# Light_Control_-_8-16_in_16-32_out_MainBl.net
KiCad netlist of a schematic drawn in Altium Designer
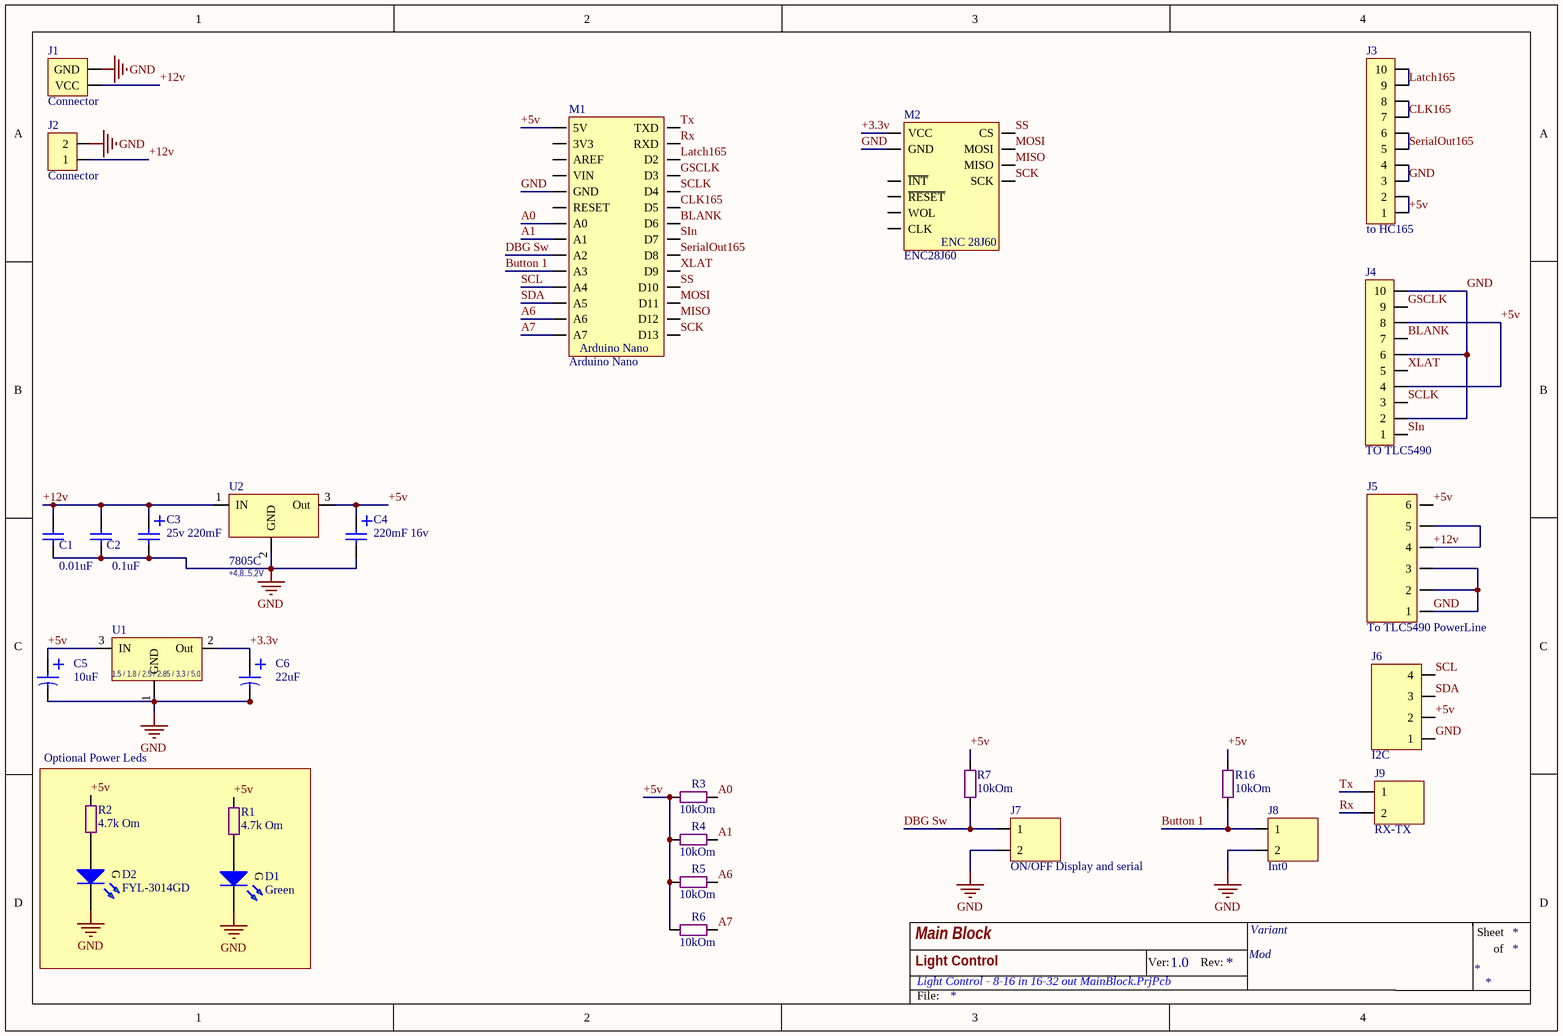
[diagram p0: Light Control - 8-16 in 16-32 out MainBlock.SchDoc]

(export (version "E")
  (design (tool "Eeschema 10.0.6"))
  (components
    (comp (ref "C1")
      (value "0.01uF")
      (footprint "Capacitor:SMD 0805 (2012)")
      (description "Capacitor")
      (libsource (lib "Capacitor") (part "Cap SMD 0402-1812"))
    )
    (comp (ref "C2")
      (value "0.1uF")
      (footprint "Capacitor:SMD 0805 (2012)")
      (description "Capacitor")
      (libsource (lib "Capacitor") (part "Cap SMD 0402-1812"))
    )
    (comp (ref "C3")
      (value "25v 220mF")
      (footprint "Capacitor:Cap E p2mm D6.5xH11")
      (description "Capacitor")
      (libsource (lib "Capacitor") (part "Cap E 220mF x 16V"))
    )
    (comp (ref "C4")
      (value "220mF 16v")
      (footprint "Capacitor:Cap E p2mm D6.5xH11")
      (description "Capacitor")
      (libsource (lib "Capacitor") (part "Cap E 220mF x 16V"))
    )
    (comp (ref "C5")
      (value "10uF")
      (footprint "Capacitor:SMD 1206 Tantal (3216)")
      (description "Capacitor")
      (libsource (lib "Capacitor") (part "Cap Tantal"))
    )
    (comp (ref "C6")
      (value "22uF")
      (footprint "Capacitor:SMD 3528 Tantal (1210)")
      (description "Capacitor")
      (libsource (lib "Capacitor") (part "Cap Tantal"))
    )
    (comp (ref "D1")
      (value "Green")
      (footprint "LED:LED SMD 0805 Green")
      (description "?2v ?20mA")
      (libsource (lib "LED") (part "Led SMD Green"))
    )
    (comp (ref "D2")
      (value "FYL-3014GD")
      (footprint "LED:LED Round 3mm Green")
      (description "2.1v 10mA, 15-30mCd")
      (libsource (lib "LED") (part "Led Round 3mm Green"))
    )
    (comp (ref "J1")
      (value "Connector")
      (footprint "Connector:DC Connector")
      (description "DC Connector")
      (libsource (lib "Connector") (part "DC Connector (PJ-002B)"))
    )
    (comp (ref "J2")
      (value "Connector")
      (footprint "Connector:DG301 5mm 2p")
      (description "DG301 series")
      (libsource (lib "Connector") (part "DG301-5.0-2P12"))
    )
    (comp (ref "J3")
      (value "to HC165")
      (footprint "Connector:LINE 2.54 x 10D (2 x 5) - BH")
      (description "Vert, Dbl line, Male")
      (libsource (lib "Connector") (part "PLD-10 (2 x 5)"))
    )
    (comp (ref "J4")
      (value "TO TLC5490")
      (footprint "Connector:LINE 2.54 x 10D (2 x 5) - BH")
      (description "Vert, Dbl line, Male")
      (libsource (lib "Connector") (part "PLD-10 (2 x 5)"))
    )
    (comp (ref "J5")
      (value "To TLC5490 PowerLine")
      (footprint "Connector:Molex Mini-Fit Jr - 6Pin R")
      (description "Right, Dbl line, Female")
      (libsource (lib "Connector") (part "Molex Mini-Fit Jr - 6 pin"))
    )
    (comp (ref "J6")
      (value "I2C")
      (footprint "Connector:Line 2.54 X 4")
      (description "Vert, Sgl line, Male")
      (libsource (lib "Connector") (part "PLS-4"))
    )
    (comp (ref "J7")
      (value "ON/OFF Display and serial")
      (footprint "Connector:Line 2.54 x 2")
      (description "Vert, Sgl line, Male")
      (libsource (lib "Connector") (part "PLS-2"))
    )
    (comp (ref "J8")
      (value "Int0")
      (footprint "Connector:Line 2.54 x 2")
      (description "Vert, Sgl line, Male")
      (libsource (lib "Connector") (part "PLS-2"))
    )
    (comp (ref "J9")
      (value "RX-TX")
      (footprint "Connector:Line 2.54 x 2")
      (description "Vert, Sgl line, Male")
      (libsource (lib "Connector") (part "PLS-2"))
    )
    (comp (ref "M1")
      (value "Arduino Nano")
      (footprint "Modules:Arduino Nano")
      (libsource (lib "Modules") (part "Arduino Nano"))
    )
    (comp (ref "M2")
      (value "ENC28J60")
      (footprint "Modules:ENC28J60 MiNi")
      (libsource (lib "Modules") (part "ENC28J60"))
    )
    (comp (ref "R1")
      (value "4.7k Om")
      (footprint "PassiveComponents:SMD 0805 (2012)")
      (libsource (lib "PassiveComponents") (part "Res All Types"))
    )
    (comp (ref "R2")
      (value "4.7k Om")
      (footprint "PassiveComponents:SMD 0805 (2012)")
      (libsource (lib "PassiveComponents") (part "Res All Types"))
    )
    (comp (ref "R3")
      (value "10kOm")
      (footprint "PassiveComponents:SMD 0805 (2012)")
      (libsource (lib "PassiveComponents") (part "Res All Types"))
    )
    (comp (ref "R4")
      (value "10kOm")
      (footprint "PassiveComponents:SMD 0805 (2012)")
      (libsource (lib "PassiveComponents") (part "Res All Types"))
    )
    (comp (ref "R5")
      (value "10kOm")
      (footprint "PassiveComponents:SMD 0805 (2012)")
      (libsource (lib "PassiveComponents") (part "Res All Types"))
    )
    (comp (ref "R6")
      (value "10kOm")
      (footprint "PassiveComponents:SMD 0805 (2012)")
      (libsource (lib "PassiveComponents") (part "Res All Types"))
    )
    (comp (ref "R7")
      (value "10kOm")
      (footprint "PassiveComponents:SMD 0805 (2012)")
      (libsource (lib "PassiveComponents") (part "Res All Types"))
    )
    (comp (ref "R16")
      (value "10kOm")
      (footprint "PassiveComponents:SMD 0805 (2012)")
      (libsource (lib "PassiveComponents") (part "Res All Types"))
    )
    (comp (ref "U1")
      (value "AMS1117 1.5 / 1.8 / 2.5 / 2.85 / 3.3 / 5.0")
      (footprint "GeneralCases:SOT-223-3 (AMS)")
      (description "Voltage Regulator SOT-223-3")
      (fields (field (name "V OUT") "1.5 / 1.8 / 2.5 / 2.85 / 3.3 / 5.0"))
      (libsource (lib "PowerAdjusment") (part "AMS1117_FIX"))
    )
    (comp (ref "U2")
      (value "7805C")
      (footprint "GeneralCases:D-PAK")
      (description "Voltage Regulator")
      (fields (field (name "MANUFACTURER") "Интеграл") (field (name "V OUT") "+4,8..5,2V"))
      (libsource (lib "PowerAdjusment") (part "7805C"))
    )
  )
  (nets
    (net (code "1") (name "/+3.3v") (class "Default")
      (node (ref "C6") (pin "VCC") (pinfunction "1_VCC") (pintype "passive"))
      (node (ref "M2") (pin "VCC") (pinfunction "VCC_VCC") (pintype "passive"))
      (node (ref "U1") (pin "2") (pinfunction "Out_2") (pintype "power_in"))
    )
    (net (code "2") (name "/+5v") (class "Default")
      (node (ref "C4") (pin "1") (pinfunction "1_1") (pintype "passive"))
      (node (ref "C5") (pin "VCC") (pinfunction "1_VCC") (pintype "passive"))
      (node (ref "J3") (pin "1") (pinfunction "1_1") (pintype "passive"))
      (node (ref "J3") (pin "2") (pinfunction "2_2") (pintype "passive"))
      (node (ref "J4") (pin "4") (pinfunction "4_4") (pintype "passive"))
      (node (ref "J4") (pin "8") (pinfunction "8_8") (pintype "passive"))
      (node (ref "J5") (pin "6") (pinfunction "6_6") (pintype "passive"))
      (node (ref "J6") (pin "2") (pinfunction "2_2") (pintype "passive"))
      (node (ref "M1") (pin "5V") (pinfunction "5V_5V") (pintype "passive"))
      (node (ref "R1") (pin "1") (pinfunction "1_1") (pintype "passive"))
      (node (ref "R16") (pin "2") (pinfunction "2_2") (pintype "passive"))
      (node (ref "R2") (pin "1") (pinfunction "1_1") (pintype "passive"))
      (node (ref "R3") (pin "2") (pinfunction "2_2") (pintype "passive"))
      (node (ref "R4") (pin "2") (pinfunction "2_2") (pintype "passive"))
      (node (ref "R5") (pin "2") (pinfunction "2_2") (pintype "passive"))
      (node (ref "R6") (pin "2") (pinfunction "2_2") (pintype "passive"))
      (node (ref "R7") (pin "2") (pinfunction "2_2") (pintype "passive"))
      (node (ref "U1") (pin "3") (pinfunction "IN_3") (pintype "power_in"))
      (node (ref "U2") (pin "3") (pinfunction "Out_3") (pintype "power_in"))
    )
    (net (code "3") (name "/+12v") (class "Default")
      (node (ref "C1") (pin "1") (pinfunction "1_1") (pintype "passive"))
      (node (ref "C2") (pin "1") (pinfunction "1_1") (pintype "passive"))
      (node (ref "C3") (pin "1") (pinfunction "1_1") (pintype "passive"))
      (node (ref "J1") (pin "VCC") (pinfunction "VCC_VCC") (pintype "passive"))
      (node (ref "J2") (pin "1") (pinfunction "1_1") (pintype "passive"))
      (node (ref "J5") (pin "4") (pinfunction "4_4") (pintype "passive"))
      (node (ref "J5") (pin "5") (pinfunction "5_5") (pintype "passive"))
      (node (ref "U2") (pin "1") (pinfunction "IN_1") (pintype "power_in"))
    )
    (net (code "4") (name "/A0") (class "Default")
      (node (ref "M1") (pin "A0") (pinfunction "A0_A0") (pintype "passive"))
      (node (ref "R3") (pin "1") (pinfunction "1_1") (pintype "passive"))
    )
    (net (code "5") (name "/A1") (class "Default")
      (node (ref "M1") (pin "A1") (pinfunction "A1_A1") (pintype "passive"))
      (node (ref "R4") (pin "1") (pinfunction "1_1") (pintype "passive"))
    )
    (net (code "6") (name "/A6") (class "Default")
      (node (ref "M1") (pin "A6") (pinfunction "A6_A6") (pintype "passive"))
      (node (ref "R5") (pin "1") (pinfunction "1_1") (pintype "passive"))
    )
    (net (code "7") (name "/A7") (class "Default")
      (node (ref "M1") (pin "A7") (pinfunction "A7_A7") (pintype "passive"))
      (node (ref "R6") (pin "1") (pinfunction "1_1") (pintype "passive"))
    )
    (net (code "8") (name "/BLANK") (class "Default")
      (node (ref "J4") (pin "7") (pinfunction "7_7") (pintype "passive"))
      (node (ref "M1") (pin "D6") (pinfunction "D6_D6") (pintype "passive"))
    )
    (net (code "9") (name "/Button 1") (class "Default")
      (node (ref "J8") (pin "1") (pinfunction "1_1") (pintype "passive"))
      (node (ref "M1") (pin "A3") (pinfunction "A3_A3") (pintype "passive"))
      (node (ref "R16") (pin "1") (pinfunction "1_1") (pintype "passive"))
    )
    (net (code "10") (name "/CLK165") (class "Default")
      (node (ref "J3") (pin "7") (pinfunction "7_7") (pintype "passive"))
      (node (ref "J3") (pin "8") (pinfunction "8_8") (pintype "passive"))
      (node (ref "M1") (pin "D5") (pinfunction "D5_D5") (pintype "passive"))
    )
    (net (code "11") (name "/DBG Sw") (class "Default")
      (node (ref "J7") (pin "1") (pinfunction "1_1") (pintype "passive"))
      (node (ref "M1") (pin "A2") (pinfunction "A2_A2") (pintype "passive"))
      (node (ref "R7") (pin "1") (pinfunction "1_1") (pintype "passive"))
    )
    (net (code "12") (name "/GSCLK") (class "Default")
      (node (ref "J4") (pin "9") (pinfunction "9_9") (pintype "passive"))
      (node (ref "M1") (pin "D3") (pinfunction "D3_D3") (pintype "passive"))
    )
    (net (code "13") (name "/Latch165") (class "Default")
      (node (ref "J3") (pin "10") (pinfunction "10_10") (pintype "passive"))
      (node (ref "J3") (pin "9") (pinfunction "9_9") (pintype "passive"))
      (node (ref "M1") (pin "D2") (pinfunction "D2_D2") (pintype "passive"))
    )
    (net (code "14") (name "/MISO") (class "Default")
      (node (ref "M1") (pin "D12") (pinfunction "D12_D12") (pintype "passive"))
      (node (ref "M2") (pin "MISO") (pinfunction "MISO_MISO") (pintype "passive"))
    )
    (net (code "15") (name "/MOSI") (class "Default")
      (node (ref "M1") (pin "D11") (pinfunction "D11_D11") (pintype "passive"))
      (node (ref "M2") (pin "MOSI") (pinfunction "MOSI_MOSI") (pintype "passive"))
    )
    (net (code "16") (name "/Rx") (class "Default")
      (node (ref "J9") (pin "2") (pinfunction "2_2") (pintype "passive"))
      (node (ref "M1") (pin "RXD") (pinfunction "RXD_RXD") (pintype "passive"))
    )
    (net (code "17") (name "/SCK") (class "Default")
      (node (ref "M1") (pin "D13") (pinfunction "D13_D13") (pintype "passive"))
      (node (ref "M2") (pin "SCK") (pinfunction "SCK_SCK") (pintype "passive"))
    )
    (net (code "18") (name "/SCL") (class "Default")
      (node (ref "J6") (pin "4") (pinfunction "4_4") (pintype "passive"))
      (node (ref "M1") (pin "A4") (pinfunction "A4_A4") (pintype "passive"))
    )
    (net (code "19") (name "/SCLK") (class "Default")
      (node (ref "J4") (pin "3") (pinfunction "3_3") (pintype "passive"))
      (node (ref "M1") (pin "D4") (pinfunction "D4_D4") (pintype "passive"))
    )
    (net (code "20") (name "/SDA") (class "Default")
      (node (ref "J6") (pin "3") (pinfunction "3_3") (pintype "passive"))
      (node (ref "M1") (pin "A5") (pinfunction "A5_A5") (pintype "passive"))
    )
    (net (code "21") (name "/SIn") (class "Default")
      (node (ref "J4") (pin "1") (pinfunction "1_1") (pintype "passive"))
      (node (ref "M1") (pin "D7") (pinfunction "D7_D7") (pintype "passive"))
    )
    (net (code "22") (name "/SS") (class "Default")
      (node (ref "M1") (pin "D10") (pinfunction "D10_D10") (pintype "passive"))
      (node (ref "M2") (pin "CS") (pinfunction "CS_CS") (pintype "passive"))
    )
    (net (code "23") (name "/SerialOut165") (class "Default")
      (node (ref "J3") (pin "5") (pinfunction "5_5") (pintype "passive"))
      (node (ref "J3") (pin "6") (pinfunction "6_6") (pintype "passive"))
      (node (ref "M1") (pin "D8") (pinfunction "D8_D8") (pintype "passive"))
    )
    (net (code "24") (name "/Tx") (class "Default")
      (node (ref "J9") (pin "1") (pinfunction "1_1") (pintype "passive"))
      (node (ref "M1") (pin "TXD") (pinfunction "TXD_TXD") (pintype "passive"))
    )
    (net (code "25") (name "/XLAT") (class "Default")
      (node (ref "J4") (pin "5") (pinfunction "5_5") (pintype "passive"))
      (node (ref "M1") (pin "D9") (pinfunction "D9_D9") (pintype "passive"))
    )
    (net (code "26") (name "GND") (class "Default")
      (node (ref "C1") (pin "2") (pinfunction "2_2") (pintype "passive"))
      (node (ref "C2") (pin "2") (pinfunction "2_2") (pintype "passive"))
      (node (ref "C3") (pin "2") (pinfunction "2_2") (pintype "passive"))
      (node (ref "C4") (pin "2") (pinfunction "2_2") (pintype "passive"))
      (node (ref "C5") (pin "GND") (pinfunction "2_GND") (pintype "passive"))
      (node (ref "C6") (pin "GND") (pinfunction "2_GND") (pintype "passive"))
      (node (ref "D1") (pin "K") (pinfunction "K_K") (pintype "passive"))
      (node (ref "D2") (pin "K") (pinfunction "K_K") (pintype "passive"))
      (node (ref "J1") (pin "GND") (pinfunction "GND_GND") (pintype "passive"))
      (node (ref "J2") (pin "2") (pinfunction "2_2") (pintype "passive"))
      (node (ref "J3") (pin "3") (pinfunction "3_3") (pintype "passive"))
      (node (ref "J3") (pin "4") (pinfunction "4_4") (pintype "passive"))
      (node (ref "J4") (pin "10") (pinfunction "10_10") (pintype "passive"))
      (node (ref "J4") (pin "2") (pinfunction "2_2") (pintype "passive"))
      (node (ref "J4") (pin "6") (pinfunction "6_6") (pintype "passive"))
      (node (ref "J5") (pin "1") (pinfunction "1_1") (pintype "passive"))
      (node (ref "J5") (pin "2") (pinfunction "2_2") (pintype "passive"))
      (node (ref "J5") (pin "3") (pinfunction "3_3") (pintype "passive"))
      (node (ref "J6") (pin "1") (pinfunction "1_1") (pintype "passive"))
      (node (ref "J7") (pin "2") (pinfunction "2_2") (pintype "passive"))
      (node (ref "J8") (pin "2") (pinfunction "2_2") (pintype "passive"))
      (node (ref "M1") (pin "GND") (pinfunction "GND_GND") (pintype "passive"))
      (node (ref "M2") (pin "GND") (pinfunction "GND_GND") (pintype "passive"))
      (node (ref "U1") (pin "1") (pinfunction "GND_1") (pintype "passive"))
      (node (ref "U2") (pin "2") (pinfunction "GND_2") (pintype "passive"))
    )
    (net (code "27") (name "Net-(D1-PadA)") (class "Default")
      (node (ref "D1") (pin "A") (pinfunction "A_A") (pintype "passive"))
      (node (ref "R1") (pin "2") (pinfunction "2_2") (pintype "passive"))
    )
    (net (code "28") (name "Net-(D2-PadA)") (class "Default")
      (node (ref "D2") (pin "A") (pinfunction "A_A") (pintype "passive"))
      (node (ref "R2") (pin "2") (pinfunction "2_2") (pintype "passive"))
    )
    (net (code "29") (name "unconnected-(M1-Pad3V3)") (class "Default")
      (node (ref "M1") (pin "3V3") (pinfunction "3V3_3V3") (pintype "passive"))
    )
    (net (code "30") (name "unconnected-(M1-PadAREF)") (class "Default")
      (node (ref "M1") (pin "AREF") (pinfunction "AREF_AREF") (pintype "passive"))
    )
    (net (code "31") (name "unconnected-(M1-PadRESET)") (class "Default")
      (node (ref "M1") (pin "RESET") (pinfunction "RESET_RESET") (pintype "passive"))
    )
    (net (code "32") (name "unconnected-(M1-PadVIN)") (class "Default")
      (node (ref "M1") (pin "VIN") (pinfunction "VIN_VIN") (pintype "passive"))
    )
    (net (code "33") (name "unconnected-(M2-PadCLK)") (class "Default")
      (node (ref "M2") (pin "CLK") (pinfunction "CLK_CLK") (pintype "passive"))
    )
    (net (code "34") (name "unconnected-(M2-PadWOL)") (class "Default")
      (node (ref "M2") (pin "WOL") (pinfunction "WOL_WOL") (pintype "passive"))
    )
    (net (code "35") (name "unconnected-(M2-~{INT}-PadINT)") (class "Default")
      (node (ref "M2") (pin "INT") (pinfunction "~{INT}_INT") (pintype "passive"))
    )
    (net (code "36") (name "unconnected-(M2-~{RESET}-PadRESET)") (class "Default")
      (node (ref "M2") (pin "RESET") (pinfunction "~{RESET}_RESET") (pintype "passive"))
    )
  )
)
